# Motor_Driver_HIP4082_Board_V1_1.net
KiCad netlist of a schematic drawn in Altium Designer
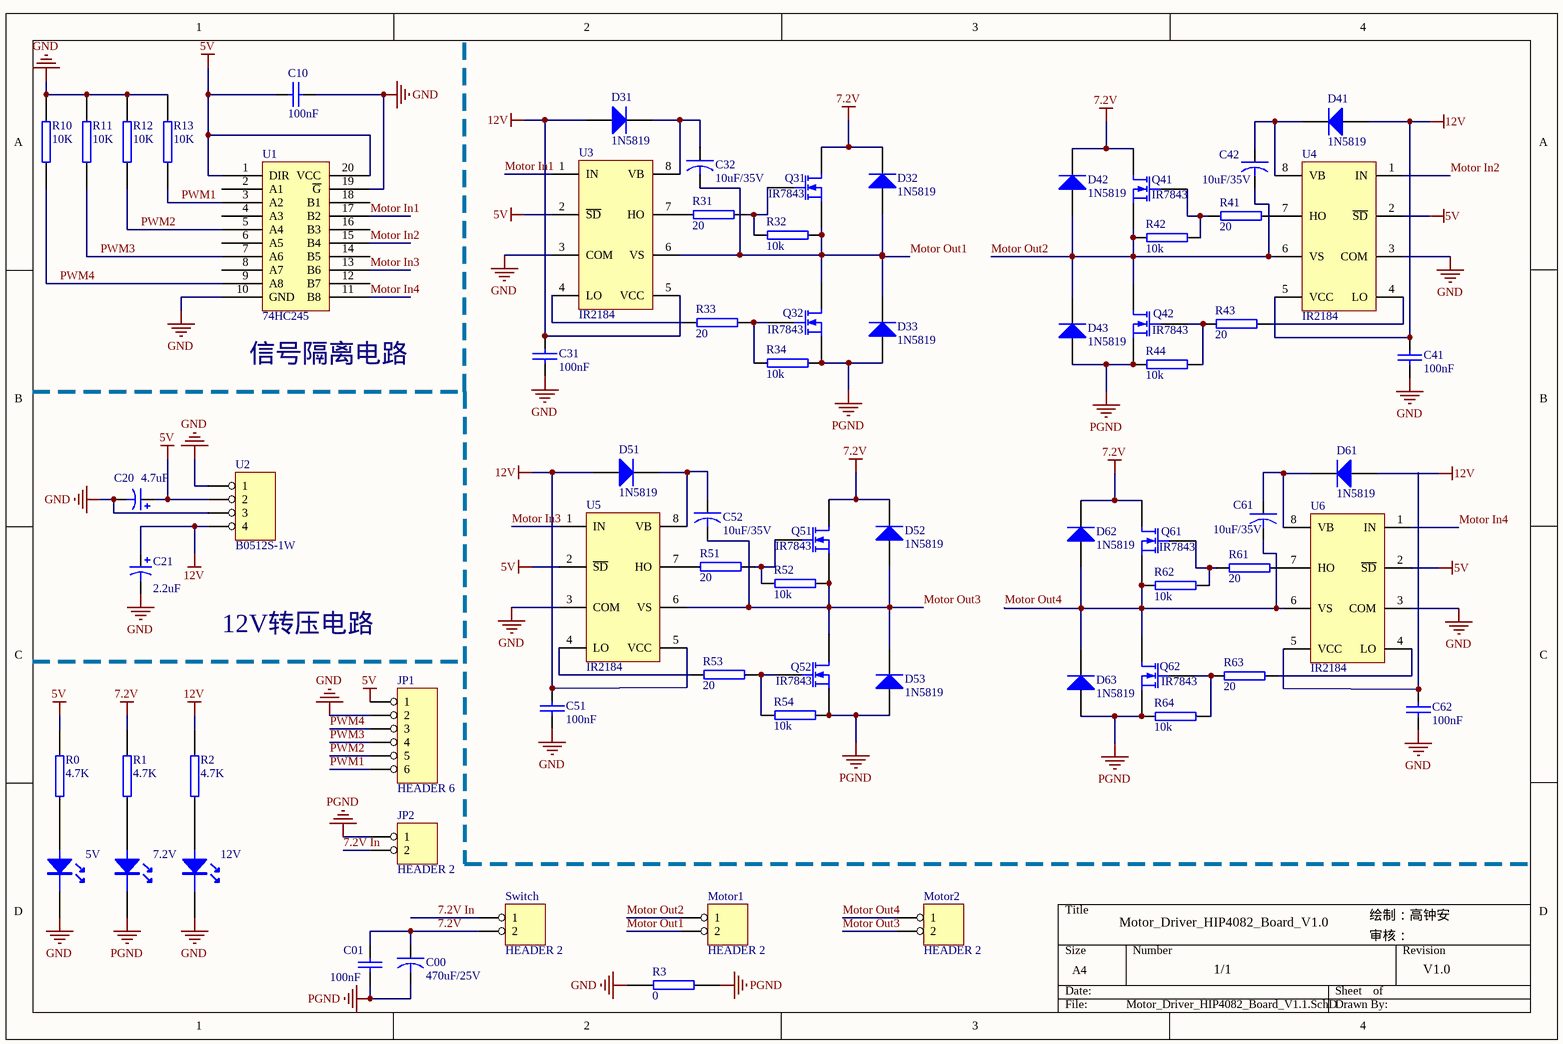
[diagram p0: Motor_Driver_HIP4082_Board_V1.1.SchDoc]

(export (version "E")
  (design (tool "Eeschema 10.0.6"))
  (components
    (comp (ref "5V") (value "~") (footprint "0805_LED_S1") (libsource (lib "Protel99Lib_SCH") (part "LED")))
    (comp (ref "7.2V") (value "~") (footprint "0805_LED_S1") (libsource (lib "Protel99Lib_SCH") (part "LED")))
    (comp (ref "12V") (value "~") (footprint "0805_LED_S1") (libsource (lib "Protel99Lib_SCH") (part "LED")))
    (comp (ref "C00")
      (value "470uF/25V")
      (footprint "RB.2/.4")
      (description "Capacitor")
      (libsource (lib "Protel99Lib_SCH") (part "CAPACITOR"))
    )
    (comp (ref "C01")
      (value "100nF")
      (footprint "0805C")
      (description "Capacitor")
      (libsource (lib "Protel99Lib_SCH") (part "CAP"))
    )
    (comp (ref "C10")
      (value "100nF")
      (footprint "0603_C")
      (description "Capacitor")
      (libsource (lib "Protel99Lib_SCH") (part "CAP"))
    )
    (comp (ref "C20")
      (value "4.7uF")
      (footprint "3528")
      (description "Polarized Capacitor (Surface Mount)")
      (fields (field (name "PUBLISHER") "Altium Limited"))
      (libsource (lib "Miscellaneous Devices") (part "Cap Pol3"))
    )
    (comp (ref "C21")
      (value "2.2uF")
      (footprint "3528")
      (description "Polarized Capacitor (Surface Mount)")
      (fields (field (name "PUBLISHER") "Altium Limited"))
      (libsource (lib "Miscellaneous Devices") (part "Cap Pol3"))
    )
    (comp (ref "C31")
      (value "100nF")
      (footprint "0805C")
      (description "Capacitor")
      (libsource (lib "Motor_Driver_IR2184") (part "CAP"))
    )
    (comp (ref "C32")
      (value "10uF/35V")
      (footprint "3528")
      (description "Capacitor")
      (libsource (lib "Motor_Driver_IR2184") (part "CAPACITOR"))
    )
    (comp (ref "C41")
      (value "100nF")
      (footprint "0805C")
      (description "Capacitor")
      (libsource (lib "Motor_Driver_IR2184") (part "CAP"))
    )
    (comp (ref "C42")
      (value "10uF/35V")
      (footprint "3528")
      (description "Capacitor")
      (libsource (lib "") (part "CAPACITOR_1"))
    )
    (comp (ref "C51")
      (value "100nF")
      (footprint "0805C")
      (description "Capacitor")
      (libsource (lib "Motor_Driver_IR2184") (part "CAP"))
    )
    (comp (ref "C52")
      (value "10uF/35V")
      (footprint "3528")
      (description "Capacitor")
      (libsource (lib "Motor_Driver_IR2184") (part "CAPACITOR"))
    )
    (comp (ref "C61")
      (value "10uF/35V")
      (footprint "3528")
      (description "Capacitor")
      (libsource (lib "") (part "CAPACITOR_1"))
    )
    (comp (ref "C62")
      (value "100nF")
      (footprint "0805C")
      (description "Capacitor")
      (libsource (lib "Motor_Driver_IR2184") (part "CAP"))
    )
    (comp (ref "D31")
      (value "1N5819")
      (footprint "3528")
      (description "Default Diode")
      (fields (field (name "PUBLISHER") "Altium Limited"))
      (libsource (lib "Motor_Driver_IR2184") (part "Diode"))
    )
    (comp (ref "D32")
      (value "1N5819")
      (footprint "3528")
      (description "Default Diode")
      (fields (field (name "PUBLISHER") "Altium Limited"))
      (libsource (lib "Motor_Driver_IR2184") (part "Diode"))
    )
    (comp (ref "D33")
      (value "1N5819")
      (footprint "3528")
      (description "Default Diode")
      (fields (field (name "PUBLISHER") "Altium Limited"))
      (libsource (lib "Motor_Driver_IR2184") (part "Diode"))
    )
    (comp (ref "D41")
      (value "1N5819")
      (footprint "3528")
      (description "Default Diode")
      (fields (field (name "PUBLISHER") "Altium Limited"))
      (libsource (lib "Motor_Driver_IR2184") (part "Diode"))
    )
    (comp (ref "D42")
      (value "1N5819")
      (footprint "3528")
      (description "Default Diode")
      (fields (field (name "PUBLISHER") "Altium Limited"))
      (libsource (lib "Motor_Driver_IR2184") (part "Diode"))
    )
    (comp (ref "D43")
      (value "1N5819")
      (footprint "3528")
      (description "Default Diode")
      (fields (field (name "PUBLISHER") "Altium Limited"))
      (libsource (lib "Motor_Driver_IR2184") (part "Diode"))
    )
    (comp (ref "D51")
      (value "1N5819")
      (footprint "3528")
      (description "Default Diode")
      (fields (field (name "PUBLISHER") "Altium Limited"))
      (libsource (lib "Motor_Driver_IR2184") (part "Diode"))
    )
    (comp (ref "D52")
      (value "1N5819")
      (footprint "3528")
      (description "Default Diode")
      (fields (field (name "PUBLISHER") "Altium Limited"))
      (libsource (lib "Motor_Driver_IR2184") (part "Diode"))
    )
    (comp (ref "D53")
      (value "1N5819")
      (footprint "3528")
      (description "Default Diode")
      (fields (field (name "PUBLISHER") "Altium Limited"))
      (libsource (lib "Motor_Driver_IR2184") (part "Diode"))
    )
    (comp (ref "D61")
      (value "1N5819")
      (footprint "3528")
      (description "Default Diode")
      (fields (field (name "PUBLISHER") "Altium Limited"))
      (libsource (lib "Motor_Driver_IR2184") (part "Diode"))
    )
    (comp (ref "D62")
      (value "1N5819")
      (footprint "3528")
      (description "Default Diode")
      (fields (field (name "PUBLISHER") "Altium Limited"))
      (libsource (lib "Motor_Driver_IR2184") (part "Diode"))
    )
    (comp (ref "D63")
      (value "1N5819")
      (footprint "3528")
      (description "Default Diode")
      (fields (field (name "PUBLISHER") "Altium Limited"))
      (libsource (lib "Motor_Driver_IR2184") (part "Diode"))
    )
    (comp (ref "JP1")
      (value "HEADER 6")
      (footprint "SIP6N")
      (libsource (lib "Protel99Lib_SCH") (part "HEADER 6"))
    )
    (comp (ref "JP2")
      (value "HEADER 2")
      (footprint "KF301-2P")
      (libsource (lib "Protel99Lib_SCH") (part "HEADER 2"))
    )
    (comp (ref "Motor1")
      (value "HEADER 2")
      (footprint "KF301-2P")
      (libsource (lib "Protel99Lib_SCH") (part "HEADER 2"))
    )
    (comp (ref "Motor2")
      (value "HEADER 2")
      (footprint "KF301-2P")
      (libsource (lib "Protel99Lib_SCH") (part "HEADER 2"))
    )
    (comp (ref "Q31")
      (value "IR7843")
      (footprint "LR7843")
      (description "N-Channel MOSFET")
      (fields (field (name "PUBLISHER") "Altium Limited"))
      (libsource (lib "Motor_Driver_IR2184") (part "MOSFET-N"))
    )
    (comp (ref "Q32")
      (value "IR7843")
      (footprint "LR7843")
      (description "N-Channel MOSFET")
      (fields (field (name "PUBLISHER") "Altium Limited"))
      (libsource (lib "Motor_Driver_IR2184") (part "MOSFET-N"))
    )
    (comp (ref "Q41")
      (value "IR7843")
      (footprint "LR7843")
      (description "N-Channel MOSFET")
      (fields (field (name "PUBLISHER") "Altium Limited"))
      (libsource (lib "Motor_Driver_IR2184") (part "MOSFET-N"))
    )
    (comp (ref "Q42")
      (value "IR7843")
      (footprint "LR7843")
      (description "N-Channel MOSFET")
      (fields (field (name "PUBLISHER") "Altium Limited"))
      (libsource (lib "Motor_Driver_IR2184") (part "MOSFET-N"))
    )
    (comp (ref "Q51")
      (value "IR7843")
      (footprint "LR7843")
      (description "N-Channel MOSFET")
      (fields (field (name "PUBLISHER") "Altium Limited"))
      (libsource (lib "Motor_Driver_IR2184") (part "MOSFET-N"))
    )
    (comp (ref "Q52")
      (value "IR7843")
      (footprint "LR7843")
      (description "N-Channel MOSFET")
      (fields (field (name "PUBLISHER") "Altium Limited"))
      (libsource (lib "Motor_Driver_IR2184") (part "MOSFET-N"))
    )
    (comp (ref "Q61")
      (value "IR7843")
      (footprint "LR7843")
      (description "N-Channel MOSFET")
      (fields (field (name "PUBLISHER") "Altium Limited"))
      (libsource (lib "Motor_Driver_IR2184") (part "MOSFET-N"))
    )
    (comp (ref "Q62")
      (value "IR7843")
      (footprint "LR7843")
      (description "N-Channel MOSFET")
      (fields (field (name "PUBLISHER") "Altium Limited"))
      (libsource (lib "Motor_Driver_IR2184") (part "MOSFET-N"))
    )
    (comp (ref "R0") (value "4.7K") (footprint "0603_R") (libsource (lib "Protel99Lib_SCH") (part "RES2")))
    (comp (ref "R1") (value "4.7K") (footprint "0603_R") (libsource (lib "Protel99Lib_SCH") (part "RES2")))
    (comp (ref "R2") (value "4.7K") (footprint "0603_R") (libsource (lib "Protel99Lib_SCH") (part "RES2")))
    (comp (ref "R3") (value "0") (footprint "0805") (libsource (lib "Protel99Lib_SCH") (part "RES2")))
    (comp (ref "R10") (value "10K") (footprint "0603_R") (libsource (lib "") (part "RES2_1")))
    (comp (ref "R11") (value "10K") (footprint "0603_R") (libsource (lib "") (part "RES2_1")))
    (comp (ref "R12") (value "10K") (footprint "0603_R") (libsource (lib "") (part "RES2_1")))
    (comp (ref "R13") (value "10K") (footprint "0603_R") (libsource (lib "") (part "RES2_1")))
    (comp (ref "R31") (value "20") (footprint "0805") (libsource (lib "Motor_Driver_IR2184") (part "RES2_1")))
    (comp (ref "R32")
      (value "10k")
      (footprint "0805")
      (libsource (lib "Motor_Driver_IR2184") (part "RES2_1"))
    )
    (comp (ref "R33") (value "20") (footprint "0805") (libsource (lib "Motor_Driver_IR2184") (part "RES2_1")))
    (comp (ref "R34")
      (value "10k")
      (footprint "0805")
      (libsource (lib "Motor_Driver_IR2184") (part "RES2_1"))
    )
    (comp (ref "R41") (value "20") (footprint "0805") (libsource (lib "Motor_Driver_IR2184") (part "RES2_1")))
    (comp (ref "R42")
      (value "10k")
      (footprint "0805")
      (libsource (lib "Motor_Driver_IR2184") (part "RES2_1"))
    )
    (comp (ref "R43") (value "20") (footprint "0805") (libsource (lib "Motor_Driver_IR2184") (part "RES2_1")))
    (comp (ref "R44")
      (value "10k")
      (footprint "0805")
      (libsource (lib "Motor_Driver_IR2184") (part "RES2_1"))
    )
    (comp (ref "R51") (value "20") (footprint "0805") (libsource (lib "Motor_Driver_IR2184") (part "RES2_1")))
    (comp (ref "R52")
      (value "10k")
      (footprint "0805")
      (libsource (lib "Motor_Driver_IR2184") (part "RES2_1"))
    )
    (comp (ref "R53") (value "20") (footprint "0805") (libsource (lib "Motor_Driver_IR2184") (part "RES2_1")))
    (comp (ref "R54")
      (value "10k")
      (footprint "0805")
      (libsource (lib "Motor_Driver_IR2184") (part "RES2_1"))
    )
    (comp (ref "R61") (value "20") (footprint "0805") (libsource (lib "Motor_Driver_IR2184") (part "RES2_1")))
    (comp (ref "R62")
      (value "10k")
      (footprint "0805")
      (libsource (lib "Motor_Driver_IR2184") (part "RES2_1"))
    )
    (comp (ref "R63") (value "20") (footprint "0805") (libsource (lib "Motor_Driver_IR2184") (part "RES2_1")))
    (comp (ref "R64")
      (value "10k")
      (footprint "0805")
      (libsource (lib "Motor_Driver_IR2184") (part "RES2_1"))
    )
    (comp (ref "Switch")
      (value "HEADER 2")
      (footprint "SWITCH-MINI")
      (libsource (lib "Protel99Lib_SCH") (part "HEADER 2"))
    )
    (comp (ref "U1") (value "74HC245") (footprint "SOP20") (libsource (lib "BaseLib_SCH") (part "74HC245")))
    (comp (ref "U2")
      (value "B0512S-1W")
      (footprint "SIP4_B_S-1W")
      (description "4 Pin Header")
      (libsource (lib "Protel99Lib_SCH") (part "4 HEADER"))
    )
    (comp (ref "U3") (value "IR2184") (footprint "SO-8") (libsource (lib "") (part "IR2184_1")))
    (comp (ref "U4")
      (value "IR2184")
      (footprint "SO-8")
      (libsource (lib "Motor_Driver_IR2184") (part "IR2184"))
    )
    (comp (ref "U5") (value "IR2184") (footprint "SO-8") (libsource (lib "") (part "IR2184_1")))
    (comp (ref "U6")
      (value "IR2184")
      (footprint "SO-8")
      (libsource (lib "Motor_Driver_IR2184") (part "IR2184"))
    )
  )
  (nets
    (net (code "1") (name "/7.2V In") (class "Default")
      (node (ref "JP2") (pin "2") (pinfunction "2_2") (pintype "passive"))
      (node (ref "Switch") (pin "1") (pinfunction "1_1") (pintype "passive"))
    )
    (net (code "2") (name "/Motor In1") (class "Default")
      (node (ref "U1") (pin "17") (pinfunction "B2_17") (pintype "passive"))
      (node (ref "U3") (pin "1") (pinfunction "IN_1") (pintype "passive"))
    )
    (net (code "3") (name "/Motor In2") (class "Default")
      (node (ref "U1") (pin "15") (pinfunction "B4_15") (pintype "passive"))
      (node (ref "U4") (pin "1") (pinfunction "IN_1") (pintype "passive"))
    )
    (net (code "4") (name "/Motor In3") (class "Default")
      (node (ref "U1") (pin "13") (pinfunction "B6_13") (pintype "passive"))
      (node (ref "U5") (pin "1") (pinfunction "IN_1") (pintype "passive"))
    )
    (net (code "5") (name "/Motor In4") (class "Default")
      (node (ref "U1") (pin "11") (pinfunction "B8_11") (pintype "passive"))
      (node (ref "U6") (pin "1") (pinfunction "IN_1") (pintype "passive"))
    )
    (net (code "6") (name "/Motor Out1") (class "Default")
      (node (ref "C32") (pin "2") (pinfunction "2_2") (pintype "passive"))
      (node (ref "D32") (pin "1") (pinfunction "A_1") (pintype "passive"))
      (node (ref "D33") (pin "2") (pinfunction "K_2") (pintype "passive"))
      (node (ref "Motor1") (pin "2") (pinfunction "2_2") (pintype "passive"))
      (node (ref "Q31") (pin "3") (pinfunction "S_3") (pintype "passive"))
      (node (ref "Q32") (pin "1") (pinfunction "D_1") (pintype "passive"))
      (node (ref "R32") (pin "1") (pinfunction "1_1") (pintype "passive"))
      (node (ref "U3") (pin "6") (pinfunction "VS_6") (pintype "passive"))
    )
    (net (code "7") (name "/Motor Out2") (class "Default")
      (node (ref "C42") (pin "2") (pinfunction "2_2") (pintype "passive"))
      (node (ref "D42") (pin "1") (pinfunction "A_1") (pintype "passive"))
      (node (ref "D43") (pin "2") (pinfunction "K_2") (pintype "passive"))
      (node (ref "Motor1") (pin "1") (pinfunction "1_1") (pintype "passive"))
      (node (ref "Q41") (pin "3") (pinfunction "S_3") (pintype "passive"))
      (node (ref "Q42") (pin "1") (pinfunction "D_1") (pintype "passive"))
      (node (ref "R42") (pin "2") (pinfunction "2_2") (pintype "passive"))
      (node (ref "U4") (pin "6") (pinfunction "VS_6") (pintype "passive"))
    )
    (net (code "8") (name "/Motor Out3") (class "Default")
      (node (ref "C52") (pin "2") (pinfunction "2_2") (pintype "passive"))
      (node (ref "D52") (pin "1") (pinfunction "A_1") (pintype "passive"))
      (node (ref "D53") (pin "2") (pinfunction "K_2") (pintype "passive"))
      (node (ref "Motor2") (pin "2") (pinfunction "2_2") (pintype "passive"))
      (node (ref "Q51") (pin "3") (pinfunction "S_3") (pintype "passive"))
      (node (ref "Q52") (pin "1") (pinfunction "D_1") (pintype "passive"))
      (node (ref "R52") (pin "1") (pinfunction "1_1") (pintype "passive"))
      (node (ref "U5") (pin "6") (pinfunction "VS_6") (pintype "passive"))
    )
    (net (code "9") (name "/Motor Out4") (class "Default")
      (node (ref "C61") (pin "2") (pinfunction "2_2") (pintype "passive"))
      (node (ref "D62") (pin "1") (pinfunction "A_1") (pintype "passive"))
      (node (ref "D63") (pin "2") (pinfunction "K_2") (pintype "passive"))
      (node (ref "Motor2") (pin "1") (pinfunction "1_1") (pintype "passive"))
      (node (ref "Q61") (pin "3") (pinfunction "S_3") (pintype "passive"))
      (node (ref "Q62") (pin "1") (pinfunction "D_1") (pintype "passive"))
      (node (ref "R62") (pin "2") (pinfunction "2_2") (pintype "passive"))
      (node (ref "U6") (pin "6") (pinfunction "VS_6") (pintype "passive"))
    )
    (net (code "10") (name "/PWM1") (class "Default")
      (node (ref "JP1") (pin "6") (pinfunction "6_6") (pintype "passive"))
      (node (ref "R13") (pin "1") (pinfunction "1_1") (pintype "passive"))
      (node (ref "U1") (pin "3") (pinfunction "A2_3") (pintype "passive"))
    )
    (net (code "11") (name "/PWM2") (class "Default")
      (node (ref "JP1") (pin "5") (pinfunction "5_5") (pintype "passive"))
      (node (ref "R12") (pin "1") (pinfunction "1_1") (pintype "passive"))
      (node (ref "U1") (pin "5") (pinfunction "A4_5") (pintype "passive"))
    )
    (net (code "12") (name "/PWM3") (class "Default")
      (node (ref "JP1") (pin "4") (pinfunction "4_4") (pintype "passive"))
      (node (ref "R11") (pin "2") (pinfunction "2_2") (pintype "passive"))
      (node (ref "U1") (pin "7") (pinfunction "A6_7") (pintype "passive"))
    )
    (net (code "13") (name "/PWM4") (class "Default")
      (node (ref "JP1") (pin "3") (pinfunction "3_3") (pintype "passive"))
      (node (ref "R10") (pin "1") (pinfunction "1_1") (pintype "passive"))
      (node (ref "U1") (pin "9") (pinfunction "A8_9") (pintype "passive"))
    )
    (net (code "14") (name "5V") (class "Default")
      (node (ref "C10") (pin "1") (pinfunction "1_1") (pintype "passive"))
      (node (ref "C20") (pin "1") (pinfunction "1_1") (pintype "passive"))
      (node (ref "JP1") (pin "1") (pinfunction "1_1") (pintype "passive"))
      (node (ref "R0") (pin "2") (pinfunction "2_2") (pintype "passive"))
      (node (ref "U1") (pin "1") (pinfunction "DIR_1") (pintype "passive"))
      (node (ref "U1") (pin "20") (pinfunction "VCC_20") (pintype "passive"))
      (node (ref "U2") (pin "2") (pinfunction "2_2") (pintype "passive"))
      (node (ref "U3") (pin "2") (pinfunction "~{SD}_2") (pintype "passive"))
      (node (ref "U4") (pin "2") (pinfunction "~{SD}_2") (pintype "passive"))
      (node (ref "U5") (pin "2") (pinfunction "~{SD}_2") (pintype "passive"))
      (node (ref "U6") (pin "2") (pinfunction "~{SD}_2") (pintype "passive"))
    )
    (net (code "15") (name "7.2V") (class "Default")
      (node (ref "C00") (pin "1") (pinfunction "1_1") (pintype "passive"))
      (node (ref "C01") (pin "2") (pinfunction "2_2") (pintype "passive"))
      (node (ref "D32") (pin "2") (pinfunction "K_2") (pintype "passive"))
      (node (ref "D42") (pin "2") (pinfunction "K_2") (pintype "passive"))
      (node (ref "D52") (pin "2") (pinfunction "K_2") (pintype "passive"))
      (node (ref "D62") (pin "2") (pinfunction "K_2") (pintype "passive"))
      (node (ref "Q31") (pin "1") (pinfunction "D_1") (pintype "passive"))
      (node (ref "Q41") (pin "1") (pinfunction "D_1") (pintype "passive"))
      (node (ref "Q51") (pin "1") (pinfunction "D_1") (pintype "passive"))
      (node (ref "Q61") (pin "1") (pinfunction "D_1") (pintype "passive"))
      (node (ref "R1") (pin "2") (pinfunction "2_2") (pintype "passive"))
      (node (ref "Switch") (pin "2") (pinfunction "2_2") (pintype "passive"))
    )
    (net (code "16") (name "12V") (class "Default")
      (node (ref "C21") (pin "1") (pinfunction "1_1") (pintype "passive"))
      (node (ref "C31") (pin "1") (pinfunction "1_1") (pintype "passive"))
      (node (ref "C41") (pin "1") (pinfunction "1_1") (pintype "passive"))
      (node (ref "C51") (pin "1") (pinfunction "1_1") (pintype "passive"))
      (node (ref "D31") (pin "1") (pinfunction "A_1") (pintype "passive"))
      (node (ref "D41") (pin "1") (pinfunction "A_1") (pintype "passive"))
      (node (ref "D51") (pin "1") (pinfunction "A_1") (pintype "passive"))
      (node (ref "D61") (pin "1") (pinfunction "A_1") (pintype "passive"))
      (node (ref "R2") (pin "2") (pinfunction "2_2") (pintype "passive"))
      (node (ref "U2") (pin "4") (pinfunction "4_4") (pintype "passive"))
      (node (ref "U3") (pin "5") (pinfunction "VCC_5") (pintype "passive"))
      (node (ref "U4") (pin "5") (pinfunction "VCC_5") (pintype "passive"))
      (node (ref "U5") (pin "5") (pinfunction "VCC_5") (pintype "passive"))
    )
    (net (code "17") (name "GND") (class "Default")
      (node (ref "12V") (pin "K") (pinfunction "2_K") (pintype "passive"))
      (node (ref "5V") (pin "K") (pinfunction "2_K") (pintype "passive"))
      (node (ref "C10") (pin "2") (pinfunction "2_2") (pintype "passive"))
      (node (ref "C20") (pin "2") (pinfunction "2_2") (pintype "passive"))
      (node (ref "C21") (pin "2") (pinfunction "2_2") (pintype "passive"))
      (node (ref "C31") (pin "2") (pinfunction "2_2") (pintype "passive"))
      (node (ref "C41") (pin "2") (pinfunction "2_2") (pintype "passive"))
      (node (ref "C51") (pin "2") (pinfunction "2_2") (pintype "passive"))
      (node (ref "C62") (pin "2") (pinfunction "2_2") (pintype "passive"))
      (node (ref "JP1") (pin "2") (pinfunction "2_2") (pintype "passive"))
      (node (ref "R10") (pin "2") (pinfunction "2_2") (pintype "passive"))
      (node (ref "R11") (pin "1") (pinfunction "1_1") (pintype "passive"))
      (node (ref "R12") (pin "2") (pinfunction "2_2") (pintype "passive"))
      (node (ref "R13") (pin "2") (pinfunction "2_2") (pintype "passive"))
      (node (ref "R3") (pin "2") (pinfunction "2_2") (pintype "passive"))
      (node (ref "U1") (pin "10") (pinfunction "GND_10") (pintype "passive"))
      (node (ref "U1") (pin "19") (pinfunction "~{G}_19") (pintype "passive"))
      (node (ref "U2") (pin "1") (pinfunction "1_1") (pintype "passive"))
      (node (ref "U2") (pin "3") (pinfunction "3_3") (pintype "passive"))
      (node (ref "U3") (pin "3") (pinfunction "COM_3") (pintype "passive"))
      (node (ref "U4") (pin "3") (pinfunction "COM_3") (pintype "passive"))
      (node (ref "U5") (pin "3") (pinfunction "COM_3") (pintype "passive"))
      (node (ref "U6") (pin "3") (pinfunction "COM_3") (pintype "passive"))
    )
    (net (code "18") (name "Net-(5V-1)") (class "Default")
      (node (ref "5V") (pin "A") (pinfunction "1_A") (pintype "passive"))
      (node (ref "R0") (pin "1") (pinfunction "1_1") (pintype "passive"))
    )
    (net (code "19") (name "Net-(7.2V-1)") (class "Default")
      (node (ref "7.2V") (pin "A") (pinfunction "1_A") (pintype "passive"))
      (node (ref "R1") (pin "1") (pinfunction "1_1") (pintype "passive"))
    )
    (net (code "20") (name "Net-(12V-1)") (class "Default")
      (node (ref "12V") (pin "A") (pinfunction "1_A") (pintype "passive"))
      (node (ref "R2") (pin "1") (pinfunction "1_1") (pintype "passive"))
    )
    (net (code "21") (name "Net-(D31-K)") (class "Default")
      (node (ref "C32") (pin "1") (pinfunction "1_1") (pintype "passive"))
      (node (ref "D31") (pin "2") (pinfunction "K_2") (pintype "passive"))
      (node (ref "U3") (pin "8") (pinfunction "VB_8") (pintype "passive"))
    )
    (net (code "22") (name "Net-(D41-K)") (class "Default")
      (node (ref "C42") (pin "1") (pinfunction "1_1") (pintype "passive"))
      (node (ref "D41") (pin "2") (pinfunction "K_2") (pintype "passive"))
      (node (ref "U4") (pin "8") (pinfunction "VB_8") (pintype "passive"))
    )
    (net (code "23") (name "Net-(D51-K)") (class "Default")
      (node (ref "C52") (pin "1") (pinfunction "1_1") (pintype "passive"))
      (node (ref "D51") (pin "2") (pinfunction "K_2") (pintype "passive"))
      (node (ref "U5") (pin "8") (pinfunction "VB_8") (pintype "passive"))
    )
    (net (code "24") (name "Net-(D61-K)") (class "Default")
      (node (ref "C61") (pin "1") (pinfunction "1_1") (pintype "passive"))
      (node (ref "D61") (pin "2") (pinfunction "K_2") (pintype "passive"))
      (node (ref "U6") (pin "8") (pinfunction "VB_8") (pintype "passive"))
    )
    (net (code "25") (name "Net-(Q31-G)") (class "Default")
      (node (ref "Q31") (pin "2") (pinfunction "G_2") (pintype "passive"))
      (node (ref "R31") (pin "2") (pinfunction "2_2") (pintype "passive"))
      (node (ref "R32") (pin "2") (pinfunction "2_2") (pintype "passive"))
    )
    (net (code "26") (name "Net-(Q32-G)") (class "Default")
      (node (ref "Q32") (pin "2") (pinfunction "G_2") (pintype "passive"))
      (node (ref "R33") (pin "2") (pinfunction "2_2") (pintype "passive"))
      (node (ref "R34") (pin "2") (pinfunction "2_2") (pintype "passive"))
    )
    (net (code "27") (name "Net-(Q41-G)") (class "Default")
      (node (ref "Q41") (pin "2") (pinfunction "G_2") (pintype "passive"))
      (node (ref "R41") (pin "2") (pinfunction "2_2") (pintype "passive"))
      (node (ref "R42") (pin "1") (pinfunction "1_1") (pintype "passive"))
    )
    (net (code "28") (name "Net-(Q42-G)") (class "Default")
      (node (ref "Q42") (pin "2") (pinfunction "G_2") (pintype "passive"))
      (node (ref "R43") (pin "2") (pinfunction "2_2") (pintype "passive"))
      (node (ref "R44") (pin "1") (pinfunction "1_1") (pintype "passive"))
    )
    (net (code "29") (name "Net-(Q51-G)") (class "Default")
      (node (ref "Q51") (pin "2") (pinfunction "G_2") (pintype "passive"))
      (node (ref "R51") (pin "2") (pinfunction "2_2") (pintype "passive"))
      (node (ref "R52") (pin "2") (pinfunction "2_2") (pintype "passive"))
    )
    (net (code "30") (name "Net-(Q52-G)") (class "Default")
      (node (ref "Q52") (pin "2") (pinfunction "G_2") (pintype "passive"))
      (node (ref "R53") (pin "2") (pinfunction "2_2") (pintype "passive"))
      (node (ref "R54") (pin "2") (pinfunction "2_2") (pintype "passive"))
    )
    (net (code "31") (name "Net-(Q61-G)") (class "Default")
      (node (ref "Q61") (pin "2") (pinfunction "G_2") (pintype "passive"))
      (node (ref "R61") (pin "2") (pinfunction "2_2") (pintype "passive"))
      (node (ref "R62") (pin "1") (pinfunction "1_1") (pintype "passive"))
    )
    (net (code "32") (name "Net-(Q62-G)") (class "Default")
      (node (ref "Q62") (pin "2") (pinfunction "G_2") (pintype "passive"))
      (node (ref "R63") (pin "2") (pinfunction "2_2") (pintype "passive"))
      (node (ref "R64") (pin "1") (pinfunction "1_1") (pintype "passive"))
    )
    (net (code "33") (name "Net-(U3-HO)") (class "Default")
      (node (ref "R31") (pin "1") (pinfunction "1_1") (pintype "passive"))
      (node (ref "U3") (pin "7") (pinfunction "HO_7") (pintype "passive"))
    )
    (net (code "34") (name "Net-(U3-LO)") (class "Default")
      (node (ref "R33") (pin "1") (pinfunction "1_1") (pintype "passive"))
      (node (ref "U3") (pin "4") (pinfunction "LO_4") (pintype "passive"))
    )
    (net (code "35") (name "Net-(U4-HO)") (class "Default")
      (node (ref "R41") (pin "1") (pinfunction "1_1") (pintype "passive"))
      (node (ref "U4") (pin "7") (pinfunction "HO_7") (pintype "passive"))
    )
    (net (code "36") (name "Net-(U4-LO)") (class "Default")
      (node (ref "R43") (pin "1") (pinfunction "1_1") (pintype "passive"))
      (node (ref "U4") (pin "4") (pinfunction "LO_4") (pintype "passive"))
    )
    (net (code "37") (name "Net-(U5-HO)") (class "Default")
      (node (ref "R51") (pin "1") (pinfunction "1_1") (pintype "passive"))
      (node (ref "U5") (pin "7") (pinfunction "HO_7") (pintype "passive"))
    )
    (net (code "38") (name "Net-(U5-LO)") (class "Default")
      (node (ref "R53") (pin "1") (pinfunction "1_1") (pintype "passive"))
      (node (ref "U5") (pin "4") (pinfunction "LO_4") (pintype "passive"))
    )
    (net (code "39") (name "Net-(U6-HO)") (class "Default")
      (node (ref "R61") (pin "1") (pinfunction "1_1") (pintype "passive"))
      (node (ref "U6") (pin "7") (pinfunction "HO_7") (pintype "passive"))
    )
    (net (code "40") (name "Net-(U6-LO)") (class "Default")
      (node (ref "R63") (pin "1") (pinfunction "1_1") (pintype "passive"))
      (node (ref "U6") (pin "4") (pinfunction "LO_4") (pintype "passive"))
    )
    (net (code "41") (name "Net-(U6-VCC)") (class "Default")
      (node (ref "C62") (pin "1") (pinfunction "1_1") (pintype "passive"))
      (node (ref "U6") (pin "5") (pinfunction "VCC_5") (pintype "passive"))
    )
    (net (code "42") (name "PGND") (class "Default")
      (node (ref "7.2V") (pin "K") (pinfunction "2_K") (pintype "passive"))
      (node (ref "C00") (pin "2") (pinfunction "2_2") (pintype "passive"))
      (node (ref "C01") (pin "1") (pinfunction "1_1") (pintype "passive"))
      (node (ref "D33") (pin "1") (pinfunction "A_1") (pintype "passive"))
      (node (ref "D43") (pin "1") (pinfunction "A_1") (pintype "passive"))
      (node (ref "D53") (pin "1") (pinfunction "A_1") (pintype "passive"))
      (node (ref "D63") (pin "1") (pinfunction "A_1") (pintype "passive"))
      (node (ref "JP2") (pin "1") (pinfunction "1_1") (pintype "passive"))
      (node (ref "Q32") (pin "3") (pinfunction "S_3") (pintype "passive"))
      (node (ref "Q42") (pin "3") (pinfunction "S_3") (pintype "passive"))
      (node (ref "Q52") (pin "3") (pinfunction "S_3") (pintype "passive"))
      (node (ref "Q62") (pin "3") (pinfunction "S_3") (pintype "passive"))
      (node (ref "R3") (pin "1") (pinfunction "1_1") (pintype "passive"))
      (node (ref "R34") (pin "1") (pinfunction "1_1") (pintype "passive"))
      (node (ref "R44") (pin "2") (pinfunction "2_2") (pintype "passive"))
      (node (ref "R54") (pin "1") (pinfunction "1_1") (pintype "passive"))
      (node (ref "R64") (pin "2") (pinfunction "2_2") (pintype "passive"))
    )
    (net (code "43") (name "unconnected-(U1-A1-Pad2)") (class "Default")
      (node (ref "U1") (pin "2") (pinfunction "A1_2") (pintype "passive"))
    )
    (net (code "44") (name "unconnected-(U1-A3-Pad4)") (class "Default")
      (node (ref "U1") (pin "4") (pinfunction "A3_4") (pintype "passive"))
    )
    (net (code "45") (name "unconnected-(U1-A5-Pad6)") (class "Default")
      (node (ref "U1") (pin "6") (pinfunction "A5_6") (pintype "passive"))
    )
    (net (code "46") (name "unconnected-(U1-A7-Pad8)") (class "Default")
      (node (ref "U1") (pin "8") (pinfunction "A7_8") (pintype "passive"))
    )
    (net (code "47") (name "unconnected-(U1-B1-Pad18)") (class "Default")
      (node (ref "U1") (pin "18") (pinfunction "B1_18") (pintype "passive"))
    )
    (net (code "48") (name "unconnected-(U1-B3-Pad16)") (class "Default")
      (node (ref "U1") (pin "16") (pinfunction "B3_16") (pintype "passive"))
    )
    (net (code "49") (name "unconnected-(U1-B5-Pad14)") (class "Default")
      (node (ref "U1") (pin "14") (pinfunction "B5_14") (pintype "passive"))
    )
    (net (code "50") (name "unconnected-(U1-B7-Pad12)") (class "Default")
      (node (ref "U1") (pin "12") (pinfunction "B7_12") (pintype "passive"))
    )
  )
)
